# Motor_Driver.net
KiCad netlist of a schematic drawn in Altium Designer
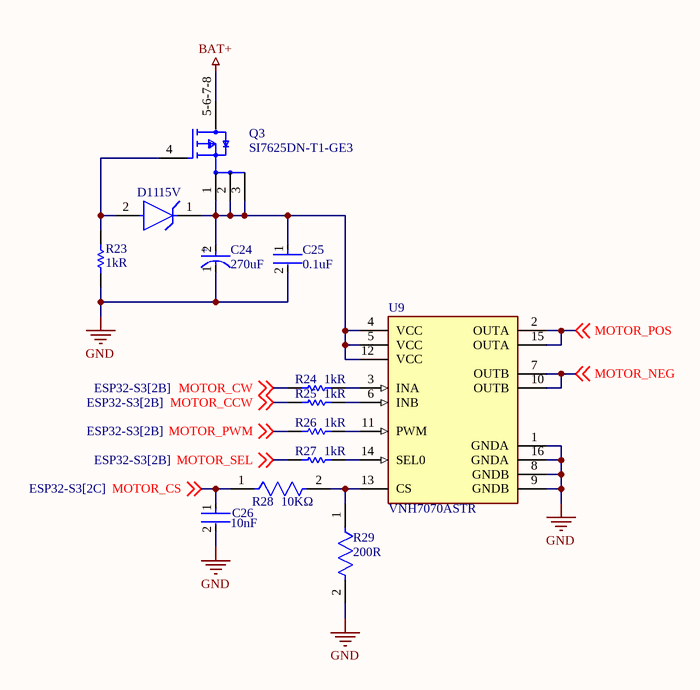
[diagram p0: Motor_Driver.SchDoc]

(export (version "E")
  (design (tool "Eeschema 10.0.6"))
  (components
    (comp (ref "C24")
      (value "EEHZA1V271V")
      (footprint "FP-EEH-G-V-MFG")
      (description "Aluminum Hybrid Polymer Capacitors 270uF 20% 35V Life 10000Hours AEC-Q200 RADIAL SMT")
      (fields (field (name "CAPACITANCE") "270uF") (field (name "TOLERANCE") "20%"))
      (libsource (lib "Altium Content Vault") (part "a00bbbee19879c290e62620ae7e47b1"))
    )
    (comp (ref "C25")
      (value "GCD21BR71H104MA01L")
      (footprint "FP-GCD21B-0_15-IPC_B")
      (description "Chip Multilayer Ceramic Capacitors for Automotive, 0805, 0.10uF, X7R, 15%, 20%, 50V, Grade 1")
      (fields (field (name "CAPACITANCE") "0.1uF"))
      (libsource (lib "Altium Content Vault") (part "b4654b650e69147ec39a6b967a45e02"))
    )
    (comp (ref "C26")
      (value "C0805C103K8RACAUTO")
      (footprint "FP-C0805C103K8RACAUTO-MFG")
      (description "C0805C103K8RACAUTO Cap, 0.01UF, 10V, Mlcc, 0805 Rohs Compliant: Yes")
      (fields (field (name "CAPACITANCE") "10nF") (field (name "TOLERANCE") "10%"))
      (libsource (lib "Altium Content Vault") (part "b4654b650e69147ec39a6b967a45e02"))
    )
    (comp (ref "D11")
      (value "MMSZ5245B-7-F")
      (footprint "FP-SOD123-MFG")
      (description "DIODE ZENER 15V 500MW SOD123")
      (fields
        (field (name "MANUFACTURER") "Diodes Inc.")
        (field (name "NOM ZENER VOLTAGE") "15V")
        (field (name "OCTOPART") "https://octopart.com/mmsz5245b-7-f-diodes+inc.-332054")
      )
      (libsource (lib "Altium Content Vault") (part "f813f71cba58e380607f5dd3caf9714"))
    )
    (comp (ref "Q3")
      (value "SI7625DN-T1-GE3")
      (footprint "FP-S16-2667-SINGLE-MFG")
      (description "SI7625DN-T1-GE3 P-Channel 30 V 7 mO 5126 nC Surface Mount Power Mosfet - PowerPAK-1212-8")
      (libsource (lib "Altium Content Vault") (part "6b55584a67f94c5edc4ba90f62f3e10"))
    )
    (comp (ref "R23")
      (value "AC0805JR-071KL")
      (footprint "RESC2013X60X35LL10T20")
      (fields (field (name "MANUFACTURER") "Yageo") (field (name "RESISTANCE") "1kR"))
      (libsource (lib "Altium Content Vault") (part "RES"))
    )
    (comp (ref "R24")
      (value "AC0805JR-071KL")
      (footprint "RESC2013X60X35LL10T20")
      (fields (field (name "MANUFACTURER") "Yageo") (field (name "RESISTANCE") "1kR"))
      (libsource (lib "Altium Content Vault") (part "RES"))
    )
    (comp (ref "R25")
      (value "AC0805JR-071KL")
      (footprint "RESC2013X60X35LL10T20")
      (fields (field (name "MANUFACTURER") "Yageo") (field (name "RESISTANCE") "1kR"))
      (libsource (lib "Altium Content Vault") (part "RES"))
    )
    (comp (ref "R26")
      (value "AC0805JR-071KL")
      (footprint "RESC2013X60X35LL10T20")
      (fields (field (name "MANUFACTURER") "Yageo") (field (name "RESISTANCE") "1kR"))
      (libsource (lib "Altium Content Vault") (part "RES"))
    )
    (comp (ref "R27")
      (value "AC0805JR-071KL")
      (footprint "RESC2013X60X35LL10T20")
      (fields (field (name "MANUFACTURER") "Yageo") (field (name "RESISTANCE") "1kR"))
      (libsource (lib "Altium Content Vault") (part "RES"))
    )
    (comp (ref "R28")
      (value "SR0805FR-4710KL")
      (footprint "FP-SR0805-MFG")
      (description "RES SMD 0805 1/2W 1% 10K OHM")
      (fields
        (field (name "RESISTANCE") "10KΩ")
        (field (name "TOLERANCE") "0.01")
        (field (name "OCTOPART") "https://octopart.com/sr0805fr-4710kl-yageo-91478094")
      )
      (libsource (lib "Altium Content Vault") (part "1029c3af85768c4190bb7ad29bc67b5"))
    )
    (comp (ref "R29")
      (value "CRCW0805200RFKEAHP")
      (footprint "FP-CRCW0805-HPe3-IPC_B")
      (description "RES Thick Film, 200Ω, 1%, 0.5W, 100ppm/°C, 0805")
      (fields (field (name "RESISTANCE") "200R") (field (name "TOLERANCE") "1%"))
      (libsource (lib "Altium Content Vault") (part "1029c3af85768c4190bb7ad29bc67b5"))
    )
    (comp (ref "U9")
      (value "VNH7070ASTR")
      (footprint "FP-SO-16N-GAPGCFT00818-MFG")
      (description "IC MOTOR DRIVER 4V-28V 16SOIC")
      (fields
        (field (name "MANUFACTURER") "STMicroelectronics")
        (field (name "OCTOPART") "https://octopart.com/vnh7070astr-stmicroelectronics-66668687")
      )
      (libsource (lib "Altium Content Vault") (part "0b40bfafcd93a4d0754fd1674b92a59"))
    )
  )
  (nets
    (net (code "1") (name "BAT+") (class "Default")
      (node (ref "Q3") (pin "5-6-7-8") (pinfunction "D_5-6-7-8") (pintype "passive"))
    )
    (net (code "2") (name "GND") (class "Default")
      (node (ref "C24") (pin "1") (pinfunction "C_1") (pintype "passive"))
      (node (ref "C25") (pin "2") (pinfunction "2_2") (pintype "passive"))
      (node (ref "C26") (pin "2") (pinfunction "2_2") (pintype "passive"))
      (node (ref "R23") (pin "1") (pinfunction "1_1") (pintype "passive"))
      (node (ref "R29") (pin "2") (pinfunction "2_2") (pintype "passive"))
      (node (ref "U9") (pin "1") (pinfunction "GNDA_1") (pintype "power_in"))
      (node (ref "U9") (pin "16") (pinfunction "GNDA_16") (pintype "power_in"))
      (node (ref "U9") (pin "8") (pinfunction "GNDB_8") (pintype "power_in"))
      (node (ref "U9") (pin "9") (pinfunction "GNDB_9") (pintype "power_in"))
    )
    (net (code "3") (name "MOTOR_CCW") (class "Default")
      (node (ref "R25") (pin "1") (pinfunction "1_1") (pintype "passive"))
    )
    (net (code "4") (name "MOTOR_CS") (class "Default")
      (node (ref "C26") (pin "1") (pinfunction "1_1") (pintype "passive"))
      (node (ref "R28") (pin "1") (pinfunction "1_1") (pintype "passive"))
    )
    (net (code "5") (name "MOTOR_CW") (class "Default")
      (node (ref "R24") (pin "1") (pinfunction "1_1") (pintype "passive"))
    )
    (net (code "6") (name "MOTOR_NEG") (class "Default")
      (node (ref "U9") (pin "10") (pinfunction "OUTB_10") (pintype "passive"))
      (node (ref "U9") (pin "7") (pinfunction "OUTB_7") (pintype "passive"))
    )
    (net (code "7") (name "MOTOR_POS") (class "Default")
      (node (ref "U9") (pin "15") (pinfunction "OUTA_15") (pintype "passive"))
      (node (ref "U9") (pin "2") (pinfunction "OUTA_2") (pintype "passive"))
    )
    (net (code "8") (name "MOTOR_PWM") (class "Default")
      (node (ref "R26") (pin "1") (pinfunction "1_1") (pintype "passive"))
    )
    (net (code "9") (name "MOTOR_SEL") (class "Default")
      (node (ref "R27") (pin "1") (pinfunction "1_1") (pintype "passive"))
    )
    (net (code "10") (name "Net-(C24-A)") (class "Default")
      (node (ref "C24") (pin "2") (pinfunction "A_2") (pintype "passive"))
      (node (ref "C25") (pin "1") (pinfunction "1_1") (pintype "passive"))
      (node (ref "D11") (pin "1") (pinfunction "C_1") (pintype "passive"))
      (node (ref "Q3") (pin "1") (pinfunction "S_1") (pintype "passive"))
      (node (ref "Q3") (pin "2") (pinfunction "S_2") (pintype "passive"))
      (node (ref "Q3") (pin "3") (pinfunction "S_3") (pintype "passive"))
      (node (ref "U9") (pin "12") (pinfunction "VCC_12") (pintype "power_in"))
      (node (ref "U9") (pin "4") (pinfunction "VCC_4") (pintype "power_in"))
      (node (ref "U9") (pin "5") (pinfunction "VCC_5") (pintype "power_in"))
    )
    (net (code "11") (name "Net-(D11-A)") (class "Default")
      (node (ref "D11") (pin "2") (pinfunction "A_2") (pintype "passive"))
      (node (ref "Q3") (pin "4") (pinfunction "G_4") (pintype "passive"))
      (node (ref "R23") (pin "2") (pinfunction "2_2") (pintype "passive"))
    )
    (net (code "12") (name "Net-(U9-CS)") (class "Default")
      (node (ref "R28") (pin "2") (pinfunction "2_2") (pintype "passive"))
      (node (ref "R29") (pin "1") (pinfunction "1_1") (pintype "passive"))
      (node (ref "U9") (pin "13") (pinfunction "CS_13") (pintype "passive"))
    )
    (net (code "13") (name "Net-(U9-INA)") (class "Default")
      (node (ref "R24") (pin "2") (pinfunction "2_2") (pintype "passive"))
      (node (ref "U9") (pin "3") (pinfunction "INA_3") (pintype "input"))
    )
    (net (code "14") (name "Net-(U9-INB)") (class "Default")
      (node (ref "R25") (pin "2") (pinfunction "2_2") (pintype "passive"))
      (node (ref "U9") (pin "6") (pinfunction "INB_6") (pintype "input"))
    )
    (net (code "15") (name "Net-(U9-PWM)") (class "Default")
      (node (ref "R26") (pin "2") (pinfunction "2_2") (pintype "passive"))
      (node (ref "U9") (pin "11") (pinfunction "PWM_11") (pintype "input"))
    )
    (net (code "16") (name "Net-(U9-SEL0)") (class "Default")
      (node (ref "R27") (pin "2") (pinfunction "2_2") (pintype "passive"))
      (node (ref "U9") (pin "14") (pinfunction "SEL0_14") (pintype "input"))
    )
  )
)
